# blt_20221101.net
KiCad netlist of a schematic drawn in EAGLE
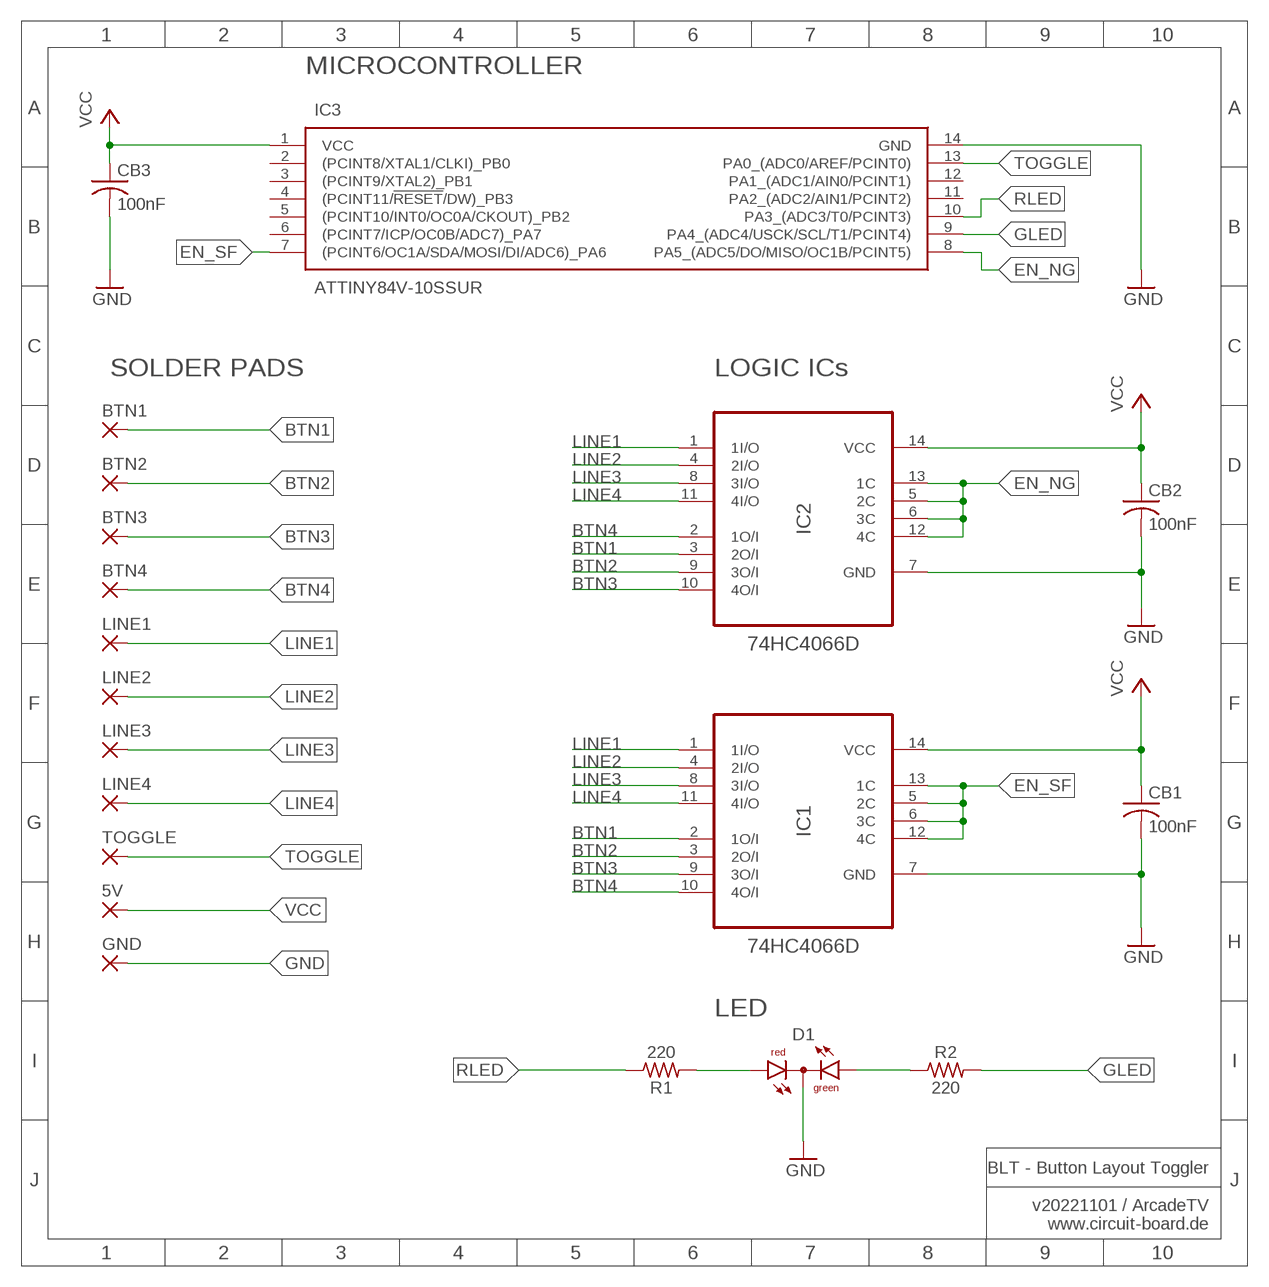
[diagram p0: schematic, sheet 1]

(export (version "E")
  (design (tool "Eeschema 10.0.6"))
  (components
    (comp (ref "5V")
      (value "WIREPADSMD2,54-5,08")
      (footprint "eagle-import:SMD2,54-5,08")
      (libsource (lib "eagle-import") (part "WIREPADSMD2,54-5,08"))
    )
    (comp (ref "BTN1")
      (value "WIREPADSMD2,54-5,08")
      (footprint "eagle-import:SMD2,54-5,08")
      (libsource (lib "eagle-import") (part "WIREPADSMD2,54-5,08"))
    )
    (comp (ref "BTN2")
      (value "WIREPADSMD2,54-5,08")
      (footprint "eagle-import:SMD2,54-5,08")
      (libsource (lib "eagle-import") (part "WIREPADSMD2,54-5,08"))
    )
    (comp (ref "BTN3")
      (value "WIREPADSMD2,54-5,08")
      (footprint "eagle-import:SMD2,54-5,08")
      (libsource (lib "eagle-import") (part "WIREPADSMD2,54-5,08"))
    )
    (comp (ref "BTN4")
      (value "WIREPADSMD2,54-5,08")
      (footprint "eagle-import:SMD2,54-5,08")
      (libsource (lib "eagle-import") (part "WIREPADSMD2,54-5,08"))
    )
    (comp (ref "CB1")
      (value "100nF")
      (footprint "eagle-import:C0805")
      (libsource (lib "eagle-import") (part "C-USC0805"))
    )
    (comp (ref "CB2")
      (value "100nF")
      (footprint "eagle-import:C0805")
      (libsource (lib "eagle-import") (part "C-USC0805"))
    )
    (comp (ref "CB3")
      (value "100nF")
      (footprint "eagle-import:C0805")
      (libsource (lib "eagle-import") (part "C-USC0805"))
    )
    (comp (ref "D1")
      (value "DUOLED2X5")
      (footprint "eagle-import:DUOLED2X5")
      (libsource (lib "eagle-import") (part "DUOLED2X5"))
    )
    (comp (ref "GND")
      (value "WIREPADSMD2,54-5,08")
      (footprint "eagle-import:SMD2,54-5,08")
      (libsource (lib "eagle-import") (part "WIREPADSMD2,54-5,08"))
    )
    (comp (ref "IC1")
      (value "74HC4066D")
      (footprint "eagle-import:SOIC127P600X175-14N")
      (libsource (lib "eagle-import") (part "74HC4066D"))
    )
    (comp (ref "IC2")
      (value "74HC4066D")
      (footprint "eagle-import:SOIC127P600X175-14N")
      (libsource (lib "eagle-import") (part "74HC4066D"))
    )
    (comp (ref "IC3")
      (value "ATTINY84V-10SSUR")
      (footprint "eagle-import:SOIC127P600X175-14N")
      (fields (field (name "MOUSER_PART_NUMBER") "556-ATTINY84V-10SSUR"))
      (libsource (lib "eagle-import") (part "ATTINY84V-10SSUR"))
    )
    (comp (ref "LINE1")
      (value "WIREPADSMD2,54-5,08")
      (footprint "eagle-import:SMD2,54-5,08")
      (libsource (lib "eagle-import") (part "WIREPADSMD2,54-5,08"))
    )
    (comp (ref "LINE2")
      (value "WIREPADSMD2,54-5,08")
      (footprint "eagle-import:SMD2,54-5,08")
      (libsource (lib "eagle-import") (part "WIREPADSMD2,54-5,08"))
    )
    (comp (ref "LINE3")
      (value "WIREPADSMD2,54-5,08")
      (footprint "eagle-import:SMD2,54-5,08")
      (libsource (lib "eagle-import") (part "WIREPADSMD2,54-5,08"))
    )
    (comp (ref "LINE4")
      (value "WIREPADSMD2,54-5,08")
      (footprint "eagle-import:SMD2,54-5,08")
      (libsource (lib "eagle-import") (part "WIREPADSMD2,54-5,08"))
    )
    (comp (ref "R1")
      (value "220")
      (footprint "eagle-import:R0805")
      (libsource (lib "eagle-import") (part "R-US_R0805"))
    )
    (comp (ref "R2")
      (value "220")
      (footprint "eagle-import:R0805")
      (libsource (lib "eagle-import") (part "R-US_R0805"))
    )
    (comp (ref "TOGGLE")
      (value "WIREPADSMD2,54-5,08")
      (footprint "eagle-import:SMD2,54-5,08")
      (libsource (lib "eagle-import") (part "WIREPADSMD2,54-5,08"))
    )
  )
  (nets
    (net (code "1") (name "BTN1") (class "Default")
      (node (ref "BTN1") (pin "1") (pinfunction "P_1") (pintype "passive"))
      (node (ref "IC1") (pin "2") (pinfunction "1O/I_2") (pintype "bidirectional"))
      (node (ref "IC2") (pin "3") (pinfunction "2O/I_3") (pintype "bidirectional"))
    )
    (net (code "2") (name "BTN2") (class "Default")
      (node (ref "BTN2") (pin "1") (pinfunction "P_1") (pintype "passive"))
      (node (ref "IC1") (pin "3") (pinfunction "2O/I_3") (pintype "bidirectional"))
      (node (ref "IC2") (pin "9") (pinfunction "3O/I_9") (pintype "bidirectional"))
    )
    (net (code "3") (name "BTN3") (class "Default")
      (node (ref "BTN3") (pin "1") (pinfunction "P_1") (pintype "passive"))
      (node (ref "IC1") (pin "9") (pinfunction "3O/I_9") (pintype "bidirectional"))
      (node (ref "IC2") (pin "10") (pinfunction "4O/I_10") (pintype "bidirectional"))
    )
    (net (code "4") (name "BTN4") (class "Default")
      (node (ref "BTN4") (pin "1") (pinfunction "P_1") (pintype "passive"))
      (node (ref "IC1") (pin "10") (pinfunction "4O/I_10") (pintype "bidirectional"))
      (node (ref "IC2") (pin "2") (pinfunction "1O/I_2") (pintype "bidirectional"))
    )
    (net (code "5") (name "EN_NG") (class "Default")
      (node (ref "IC2") (pin "12") (pinfunction "4C_12") (pintype "bidirectional"))
      (node (ref "IC2") (pin "13") (pinfunction "1C_13") (pintype "bidirectional"))
      (node (ref "IC2") (pin "5") (pinfunction "2C_5") (pintype "bidirectional"))
      (node (ref "IC2") (pin "6") (pinfunction "3C_6") (pintype "bidirectional"))
      (node (ref "IC3") (pin "8") (pinfunction "PA5_(ADC5/DO/MISO/OC1B/PCINT5)_8") (pintype "bidirectional"))
    )
    (net (code "6") (name "EN_SF") (class "Default")
      (node (ref "IC1") (pin "12") (pinfunction "4C_12") (pintype "bidirectional"))
      (node (ref "IC1") (pin "13") (pinfunction "1C_13") (pintype "bidirectional"))
      (node (ref "IC1") (pin "5") (pinfunction "2C_5") (pintype "bidirectional"))
      (node (ref "IC1") (pin "6") (pinfunction "3C_6") (pintype "bidirectional"))
      (node (ref "IC3") (pin "7") (pinfunction "(PCINT6/OC1A/SDA/MOSI/DI/ADC6)_PA6_7") (pintype "bidirectional"))
    )
    (net (code "7") (name "GLED") (class "Default")
      (node (ref "IC3") (pin "9") (pinfunction "PA4_(ADC4/USCK/SCL/T1/PCINT4)_9") (pintype "bidirectional"))
      (node (ref "R2") (pin "2") (pinfunction "2_2") (pintype "passive"))
    )
    (net (code "8") (name "GND") (class "Default")
      (node (ref "CB1") (pin "2") (pinfunction "2_2") (pintype "passive"))
      (node (ref "CB2") (pin "2") (pinfunction "2_2") (pintype "passive"))
      (node (ref "CB3") (pin "2") (pinfunction "2_2") (pintype "passive"))
      (node (ref "D1") (pin "K") (pinfunction "C_K") (pintype "passive"))
      (node (ref "GND") (pin "1") (pinfunction "P_1") (pintype "passive"))
      (node (ref "IC1") (pin "7") (pinfunction "GND_7") (pintype "bidirectional"))
      (node (ref "IC2") (pin "7") (pinfunction "GND_7") (pintype "bidirectional"))
      (node (ref "IC3") (pin "14") (pinfunction "GND_14") (pintype "bidirectional"))
    )
    (net (code "9") (name "LINE1") (class "Default")
      (node (ref "IC1") (pin "1") (pinfunction "1I/O_1") (pintype "bidirectional"))
      (node (ref "IC2") (pin "1") (pinfunction "1I/O_1") (pintype "bidirectional"))
      (node (ref "LINE1") (pin "1") (pinfunction "P_1") (pintype "passive"))
    )
    (net (code "10") (name "LINE2") (class "Default")
      (node (ref "IC1") (pin "4") (pinfunction "2I/O_4") (pintype "bidirectional"))
      (node (ref "IC2") (pin "4") (pinfunction "2I/O_4") (pintype "bidirectional"))
      (node (ref "LINE2") (pin "1") (pinfunction "P_1") (pintype "passive"))
    )
    (net (code "11") (name "LINE3") (class "Default")
      (node (ref "IC1") (pin "8") (pinfunction "3I/O_8") (pintype "bidirectional"))
      (node (ref "IC2") (pin "8") (pinfunction "3I/O_8") (pintype "bidirectional"))
      (node (ref "LINE3") (pin "1") (pinfunction "P_1") (pintype "passive"))
    )
    (net (code "12") (name "LINE4") (class "Default")
      (node (ref "IC1") (pin "11") (pinfunction "4I/O_11") (pintype "bidirectional"))
      (node (ref "IC2") (pin "11") (pinfunction "4I/O_11") (pintype "bidirectional"))
      (node (ref "LINE4") (pin "1") (pinfunction "P_1") (pintype "passive"))
    )
    (net (code "13") (name "Net-(D1-PadAG)") (class "Default")
      (node (ref "D1") (pin "AG") (pinfunction "AG_AG") (pintype "passive"))
      (node (ref "R2") (pin "1") (pinfunction "1_1") (pintype "passive"))
    )
    (net (code "14") (name "Net-(D1-PadAR)") (class "Default")
      (node (ref "D1") (pin "AR") (pinfunction "AR_AR") (pintype "passive"))
      (node (ref "R1") (pin "2") (pinfunction "2_2") (pintype "passive"))
    )
    (net (code "15") (name "RLED") (class "Default")
      (node (ref "IC3") (pin "10") (pinfunction "PA3_(ADC3/T0/PCINT3)_10") (pintype "bidirectional"))
      (node (ref "R1") (pin "1") (pinfunction "1_1") (pintype "passive"))
    )
    (net (code "16") (name "TOGGLE") (class "Default")
      (node (ref "IC3") (pin "13") (pinfunction "PA0_(ADC0/AREF/PCINT0)_13") (pintype "bidirectional"))
      (node (ref "TOGGLE") (pin "1") (pinfunction "P_1") (pintype "passive"))
    )
    (net (code "17") (name "VCC") (class "Default")
      (node (ref "5V") (pin "1") (pinfunction "P_1") (pintype "passive"))
      (node (ref "CB1") (pin "1") (pinfunction "1_1") (pintype "passive"))
      (node (ref "CB2") (pin "1") (pinfunction "1_1") (pintype "passive"))
      (node (ref "CB3") (pin "1") (pinfunction "1_1") (pintype "passive"))
      (node (ref "IC1") (pin "14") (pinfunction "VCC_14") (pintype "bidirectional"))
      (node (ref "IC2") (pin "14") (pinfunction "VCC_14") (pintype "bidirectional"))
      (node (ref "IC3") (pin "1") (pinfunction "VCC_1") (pintype "bidirectional"))
    )
    (net (code "18") (name "unconnected-(IC3-(PCINT7{slash}ICP{slash}OC0B{slash}ADC7)_PA7-Pad6)") (class "Default")
      (node (ref "IC3") (pin "6") (pinfunction "(PCINT7/ICP/OC0B/ADC7)_PA7_6") (pintype "bidirectional"))
    )
    (net (code "19") (name "unconnected-(IC3-(PCINT8{slash}XTAL1{slash}CLKI)_PB0-Pad2)") (class "Default")
      (node (ref "IC3") (pin "2") (pinfunction "(PCINT8/XTAL1/CLKI)_PB0_2") (pintype "bidirectional"))
    )
    (net (code "20") (name "unconnected-(IC3-(PCINT9{slash}XTAL2)_PB1-Pad3)") (class "Default")
      (node (ref "IC3") (pin "3") (pinfunction "(PCINT9/XTAL2)_PB1_3") (pintype "bidirectional"))
    )
    (net (code "21") (name "unconnected-(IC3-(PCINT10{slash}INT0{slash}OC0A{slash}CKOUT)_PB2-Pad5)") (class "Default")
      (node (ref "IC3") (pin "5") (pinfunction "(PCINT10/INT0/OC0A/CKOUT)_PB2_5") (pintype "bidirectional"))
    )
    (net (code "22") (name "unconnected-(IC3-(PCINT11{slash}~{RESET}{slash}DW)_PB3-Pad4)") (class "Default")
      (node (ref "IC3") (pin "4") (pinfunction "(PCINT11/~{RESET}/DW)_PB3_4") (pintype "bidirectional"))
    )
    (net (code "23") (name "unconnected-(IC3-PA1_(ADC1{slash}AIN0{slash}PCINT1)-Pad12)") (class "Default")
      (node (ref "IC3") (pin "12") (pinfunction "PA1_(ADC1/AIN0/PCINT1)_12") (pintype "bidirectional"))
    )
    (net (code "24") (name "unconnected-(IC3-PA2_(ADC2{slash}AIN1{slash}PCINT2)-Pad11)") (class "Default")
      (node (ref "IC3") (pin "11") (pinfunction "PA2_(ADC2/AIN1/PCINT2)_11") (pintype "bidirectional"))
    )
  )
)
